# Slave3.net
KiCad netlist of a schematic drawn in Altium Designer
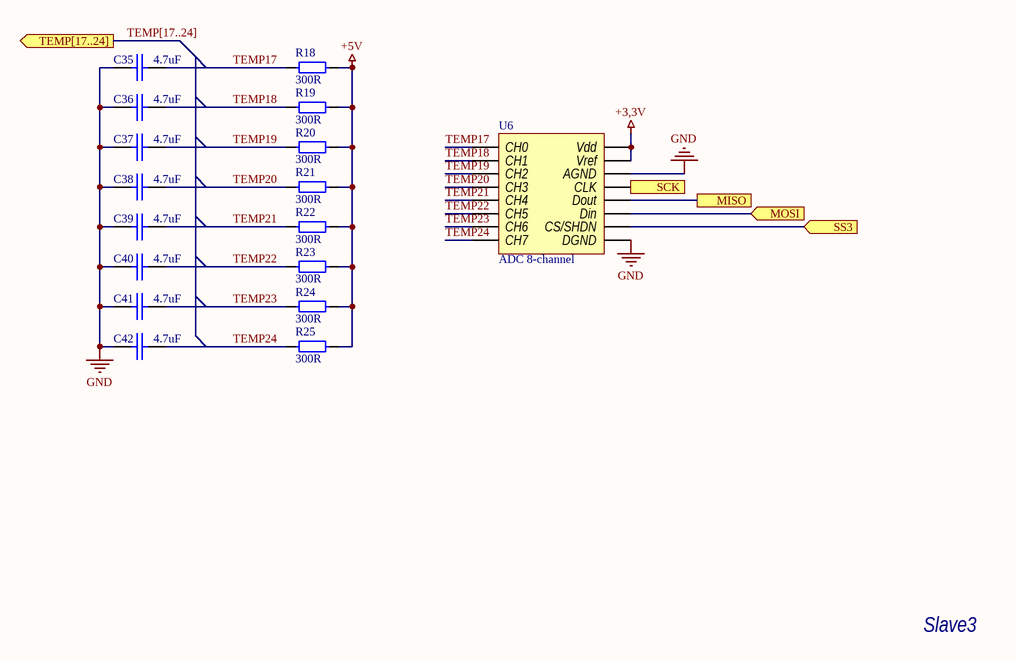
[diagram p0: Slave3.SchDoc]

(export (version "E")
  (design (tool "Eeschema 10.0.6"))
  (components
    (comp (ref "C35")
      (value "4.7uF")
      (footprint "0603 Capicator")
      (description "4.7uF X5R 25V 10% 0603")
      (fields
        (field (name "MANUFACTURER") "Murata Manufacturing")
        (field (name "PART NUMBER") "GRM188R61E475KE11D")
      )
      (libsource (lib "БУС") (part "Cap 4.7uF (0603)"))
    )
    (comp (ref "C36")
      (value "4.7uF")
      (footprint "0603 Capicator")
      (description "4.7uF X5R 25V 10% 0603")
      (fields
        (field (name "MANUFACTURER") "Murata Manufacturing")
        (field (name "PART NUMBER") "GRM188R61E475KE11D")
      )
      (libsource (lib "БУС") (part "Cap 4.7uF (0603)"))
    )
    (comp (ref "C37")
      (value "4.7uF")
      (footprint "0603 Capicator")
      (description "4.7uF X5R 25V 10% 0603")
      (fields
        (field (name "MANUFACTURER") "Murata Manufacturing")
        (field (name "PART NUMBER") "GRM188R61E475KE11D")
      )
      (libsource (lib "БУС") (part "Cap 4.7uF (0603)"))
    )
    (comp (ref "C38")
      (value "4.7uF")
      (footprint "0603 Capicator")
      (description "4.7uF X5R 25V 10% 0603")
      (fields
        (field (name "MANUFACTURER") "Murata Manufacturing")
        (field (name "PART NUMBER") "GRM188R61E475KE11D")
      )
      (libsource (lib "БУС") (part "Cap 4.7uF (0603)"))
    )
    (comp (ref "C39")
      (value "4.7uF")
      (footprint "0603 Capicator")
      (description "4.7uF X5R 25V 10% 0603")
      (fields
        (field (name "MANUFACTURER") "Murata Manufacturing")
        (field (name "PART NUMBER") "GRM188R61E475KE11D")
      )
      (libsource (lib "БУС") (part "Cap 4.7uF (0603)"))
    )
    (comp (ref "C40")
      (value "4.7uF")
      (footprint "0603 Capicator")
      (description "4.7uF X5R 25V 10% 0603")
      (fields
        (field (name "MANUFACTURER") "Murata Manufacturing")
        (field (name "PART NUMBER") "GRM188R61E475KE11D")
      )
      (libsource (lib "БУС") (part "Cap 4.7uF (0603)"))
    )
    (comp (ref "C41")
      (value "4.7uF")
      (footprint "0603 Capicator")
      (description "4.7uF X5R 25V 10% 0603")
      (fields
        (field (name "MANUFACTURER") "Murata Manufacturing")
        (field (name "PART NUMBER") "GRM188R61E475KE11D")
      )
      (libsource (lib "БУС") (part "Cap 4.7uF (0603)"))
    )
    (comp (ref "C42")
      (value "4.7uF")
      (footprint "0603 Capicator")
      (description "4.7uF X5R 25V 10% 0603")
      (fields
        (field (name "MANUFACTURER") "Murata Manufacturing")
        (field (name "PART NUMBER") "GRM188R61E475KE11D")
      )
      (libsource (lib "БУС") (part "Cap 4.7uF (0603)"))
    )
    (comp (ref "R18")
      (value "300R")
      (footprint "0603 Resistor")
      (description "0.1W 0603 300R, 1%")
      (fields (field (name "PART NUMBER") "RC0603FR-07360RL") (field (name "MANUFACTURER") "Taiwan"))
      (libsource (lib "БУС") (part "Res 300R (0603)"))
    )
    (comp (ref "R19")
      (value "300R")
      (footprint "0603 Resistor")
      (description "0.1W 0603 300R, 1%")
      (fields (field (name "PART NUMBER") "RC0603FR-07360RL") (field (name "MANUFACTURER") "Taiwan"))
      (libsource (lib "БУС") (part "Res 300R (0603)"))
    )
    (comp (ref "R20")
      (value "300R")
      (footprint "0603 Resistor")
      (description "0.1W 0603 300R, 1%")
      (fields (field (name "PART NUMBER") "RC0603FR-07360RL") (field (name "MANUFACTURER") "Taiwan"))
      (libsource (lib "БУС") (part "Res 300R (0603)"))
    )
    (comp (ref "R21")
      (value "300R")
      (footprint "0603 Resistor")
      (description "0.1W 0603 300R, 1%")
      (fields (field (name "PART NUMBER") "RC0603FR-07360RL") (field (name "MANUFACTURER") "Taiwan"))
      (libsource (lib "БУС") (part "Res 300R (0603)"))
    )
    (comp (ref "R22")
      (value "300R")
      (footprint "0603 Resistor")
      (description "0.1W 0603 300R, 1%")
      (fields (field (name "PART NUMBER") "RC0603FR-07360RL") (field (name "MANUFACTURER") "Taiwan"))
      (libsource (lib "БУС") (part "Res 300R (0603)"))
    )
    (comp (ref "R23")
      (value "300R")
      (footprint "0603 Resistor")
      (description "0.1W 0603 300R, 1%")
      (fields (field (name "PART NUMBER") "RC0603FR-07360RL") (field (name "MANUFACTURER") "Taiwan"))
      (libsource (lib "БУС") (part "Res 300R (0603)"))
    )
    (comp (ref "R24")
      (value "300R")
      (footprint "0603 Resistor")
      (description "0.1W 0603 300R, 1%")
      (fields (field (name "PART NUMBER") "RC0603FR-07360RL") (field (name "MANUFACTURER") "Taiwan"))
      (libsource (lib "БУС") (part "Res 300R (0603)"))
    )
    (comp (ref "R25")
      (value "300R")
      (footprint "0603 Resistor")
      (description "0.1W 0603 300R, 1%")
      (fields (field (name "PART NUMBER") "RC0603FR-07360RL") (field (name "MANUFACTURER") "Taiwan"))
      (libsource (lib "БУС") (part "Res 300R (0603)"))
    )
    (comp (ref "U6")
      (value "ADC 8-channel")
      (footprint "SOIC-16")
      (description "A/D converter with SPI serial interface")
      (fields (field (name "MANUFACTURER") "Microchip") (field (name "PART NUMBER") "MCP3008-I/SL"))
      (libsource (lib "БУС") (part "MCP3008-I/SL"))
    )
  )
  (nets
    (net (code "1") (name "+3,3V") (class "Default")
      (node (ref "U6") (pin "15") (pinfunction "Vref_15") (pintype "passive"))
      (node (ref "U6") (pin "16") (pinfunction "Vdd_16") (pintype "passive"))
    )
    (net (code "2") (name "+5V") (class "Default")
      (node (ref "R18") (pin "2") (pinfunction "2_2") (pintype "passive"))
      (node (ref "R19") (pin "2") (pinfunction "2_2") (pintype "passive"))
      (node (ref "R20") (pin "2") (pinfunction "2_2") (pintype "passive"))
      (node (ref "R21") (pin "2") (pinfunction "2_2") (pintype "passive"))
      (node (ref "R22") (pin "2") (pinfunction "2_2") (pintype "passive"))
      (node (ref "R23") (pin "2") (pinfunction "2_2") (pintype "passive"))
      (node (ref "R24") (pin "2") (pinfunction "2_2") (pintype "passive"))
      (node (ref "R25") (pin "2") (pinfunction "2_2") (pintype "passive"))
    )
    (net (code "3") (name "/MISO") (class "Default")
      (node (ref "U6") (pin "12") (pinfunction "Dout_12") (pintype "passive"))
    )
    (net (code "4") (name "/MOSI") (class "Default")
      (node (ref "U6") (pin "11") (pinfunction "Din_11") (pintype "passive"))
    )
    (net (code "5") (name "/SCK") (class "Default")
      (node (ref "U6") (pin "13") (pinfunction "CLK_13") (pintype "passive"))
    )
    (net (code "6") (name "/SS3") (class "Default")
      (node (ref "U6") (pin "10") (pinfunction "CS/SHDN_10") (pintype "passive"))
    )
    (net (code "7") (name "/TEMP17") (class "Default")
      (node (ref "C35") (pin "2") (pinfunction "2_2") (pintype "passive"))
      (node (ref "R18") (pin "1") (pinfunction "1_1") (pintype "passive"))
      (node (ref "U6") (pin "1") (pinfunction "CH0_1") (pintype "passive"))
    )
    (net (code "8") (name "/TEMP18") (class "Default")
      (node (ref "C36") (pin "2") (pinfunction "2_2") (pintype "passive"))
      (node (ref "R19") (pin "1") (pinfunction "1_1") (pintype "passive"))
      (node (ref "U6") (pin "2") (pinfunction "CH1_2") (pintype "passive"))
    )
    (net (code "9") (name "/TEMP19") (class "Default")
      (node (ref "C37") (pin "2") (pinfunction "2_2") (pintype "passive"))
      (node (ref "R20") (pin "1") (pinfunction "1_1") (pintype "passive"))
      (node (ref "U6") (pin "3") (pinfunction "CH2_3") (pintype "passive"))
    )
    (net (code "10") (name "/TEMP20") (class "Default")
      (node (ref "C38") (pin "2") (pinfunction "2_2") (pintype "passive"))
      (node (ref "R21") (pin "1") (pinfunction "1_1") (pintype "passive"))
      (node (ref "U6") (pin "4") (pinfunction "CH3_4") (pintype "passive"))
    )
    (net (code "11") (name "/TEMP21") (class "Default")
      (node (ref "C39") (pin "2") (pinfunction "2_2") (pintype "passive"))
      (node (ref "R22") (pin "1") (pinfunction "1_1") (pintype "passive"))
      (node (ref "U6") (pin "5") (pinfunction "CH4_5") (pintype "passive"))
    )
    (net (code "12") (name "/TEMP22") (class "Default")
      (node (ref "C40") (pin "2") (pinfunction "2_2") (pintype "passive"))
      (node (ref "R23") (pin "1") (pinfunction "1_1") (pintype "passive"))
      (node (ref "U6") (pin "6") (pinfunction "CH5_6") (pintype "passive"))
    )
    (net (code "13") (name "/TEMP23") (class "Default")
      (node (ref "C41") (pin "2") (pinfunction "2_2") (pintype "passive"))
      (node (ref "R24") (pin "1") (pinfunction "1_1") (pintype "passive"))
      (node (ref "U6") (pin "7") (pinfunction "CH6_7") (pintype "passive"))
    )
    (net (code "14") (name "/TEMP24") (class "Default")
      (node (ref "C42") (pin "2") (pinfunction "2_2") (pintype "passive"))
      (node (ref "R25") (pin "1") (pinfunction "1_1") (pintype "passive"))
      (node (ref "U6") (pin "8") (pinfunction "CH7_8") (pintype "passive"))
    )
    (net (code "16") (name "GND") (class "Default")
      (node (ref "C35") (pin "1") (pinfunction "1_1") (pintype "passive"))
      (node (ref "C36") (pin "1") (pinfunction "1_1") (pintype "passive"))
      (node (ref "C37") (pin "1") (pinfunction "1_1") (pintype "passive"))
      (node (ref "C38") (pin "1") (pinfunction "1_1") (pintype "passive"))
      (node (ref "C39") (pin "1") (pinfunction "1_1") (pintype "passive"))
      (node (ref "C40") (pin "1") (pinfunction "1_1") (pintype "passive"))
      (node (ref "C41") (pin "1") (pinfunction "1_1") (pintype "passive"))
      (node (ref "C42") (pin "1") (pinfunction "1_1") (pintype "passive"))
      (node (ref "U6") (pin "14") (pinfunction "AGND_14") (pintype "passive"))
      (node (ref "U6") (pin "9") (pinfunction "DGND_9") (pintype "passive"))
    )
  )
)
